# pump_control.net
KiCad netlist of a schematic drawn in EAGLE
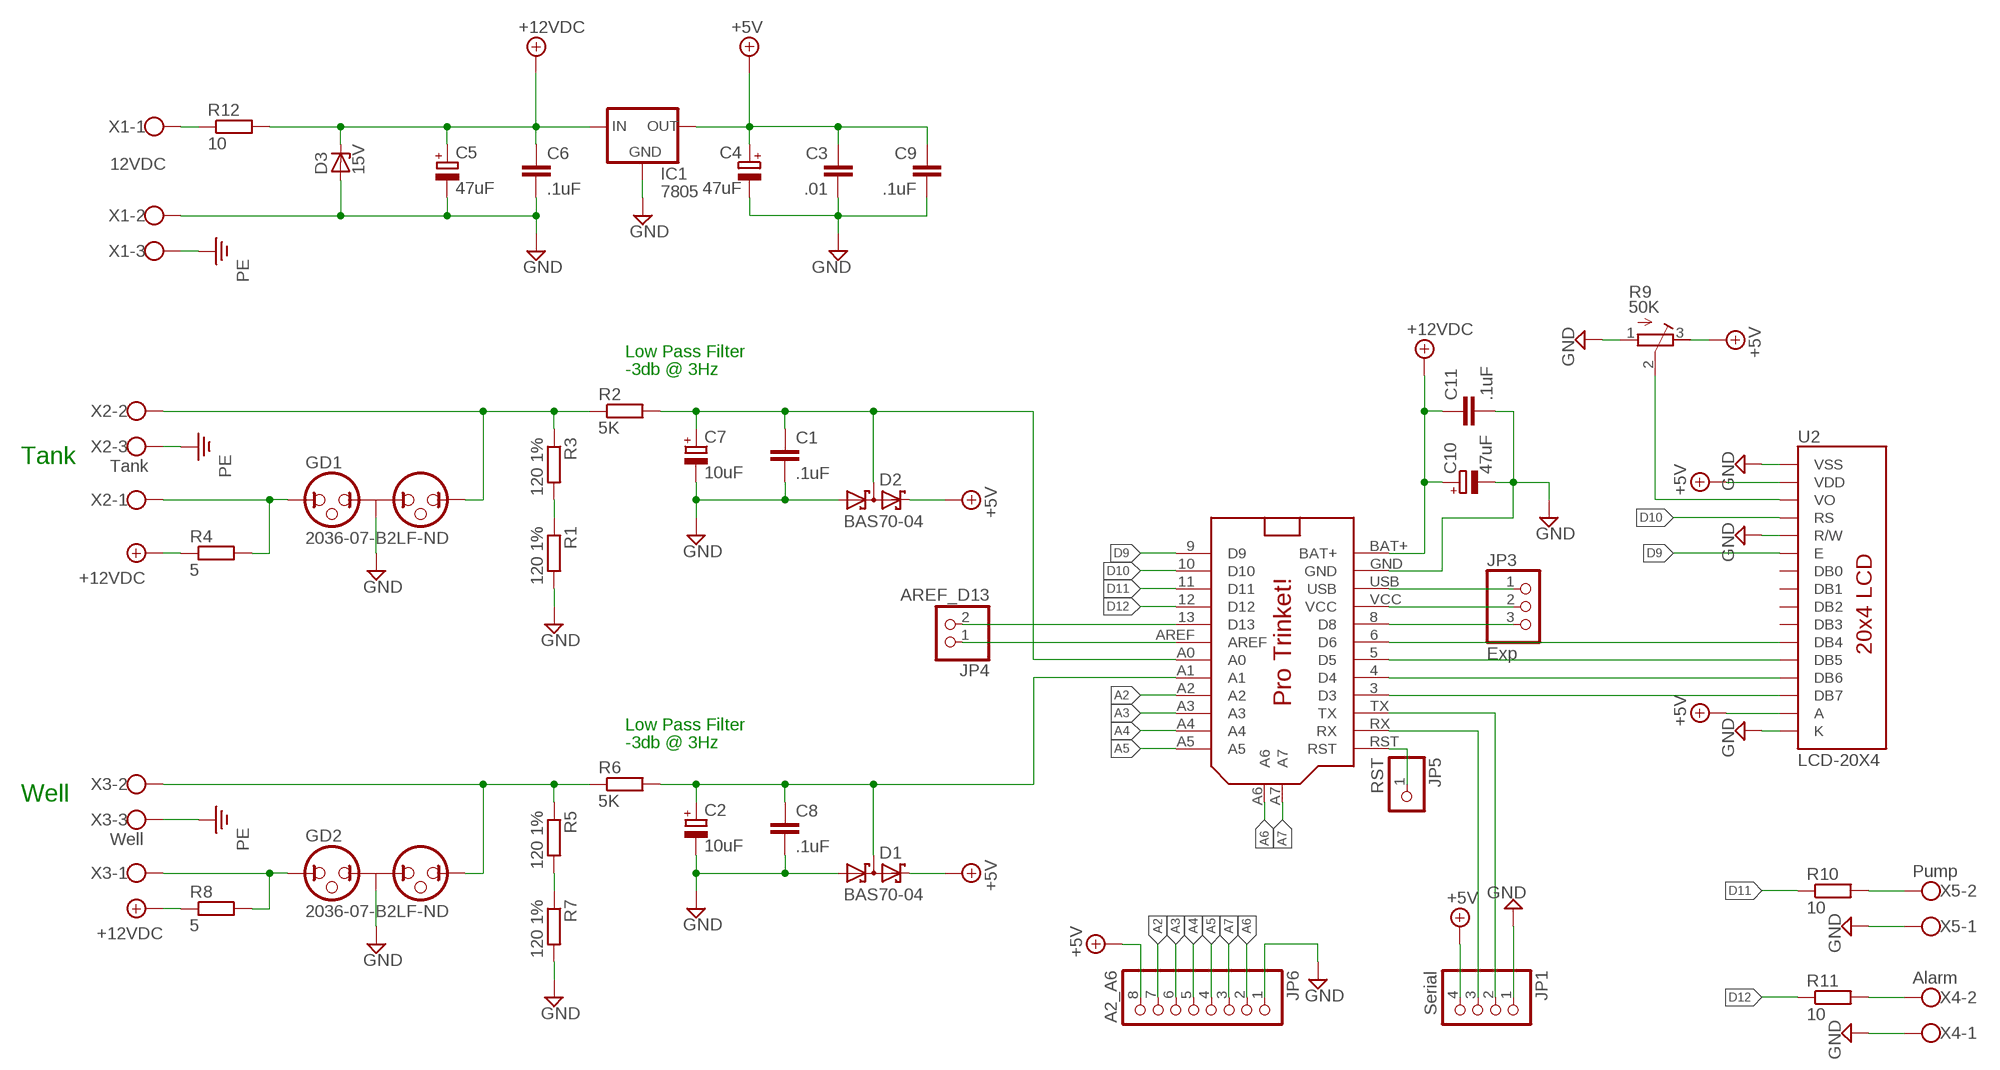
[diagram p0: schematic, sheet 1]

(export (version "E")
  (design (tool "Eeschema 10.0.6"))
  (components
    (comp (ref "C1")
      (value ".1uF")
      (footprint "eagle-import:C050-025X075")
      (libsource (lib "eagle-import") (part "C-EU050-025X075"))
    )
    (comp (ref "C2")
      (value "10uF")
      (footprint "eagle-import:E3,5-8")
      (libsource (lib "eagle-import") (part "CPOL-EUE3.5-8"))
    )
    (comp (ref "C3")
      (value ".01")
      (footprint "eagle-import:C050-025X075")
      (libsource (lib "eagle-import") (part "C-EU050-025X075"))
    )
    (comp (ref "C4")
      (value "47uF")
      (footprint "eagle-import:E3,5-8")
      (libsource (lib "eagle-import") (part "CPOL-EUE3.5-8"))
    )
    (comp (ref "C5")
      (value "47uF")
      (footprint "eagle-import:E3,5-8")
      (libsource (lib "eagle-import") (part "CPOL-EUE3.5-8"))
    )
    (comp (ref "C6")
      (value ".1uF")
      (footprint "eagle-import:C050-025X075")
      (libsource (lib "eagle-import") (part "C-EU050-025X075"))
    )
    (comp (ref "C7")
      (value "10uF")
      (footprint "eagle-import:E3,5-8")
      (libsource (lib "eagle-import") (part "CPOL-EUE3.5-8"))
    )
    (comp (ref "C8")
      (value ".1uF")
      (footprint "eagle-import:C050-025X075")
      (libsource (lib "eagle-import") (part "C-EU050-025X075"))
    )
    (comp (ref "C9")
      (value ".1uF")
      (footprint "eagle-import:C050-025X075")
      (libsource (lib "eagle-import") (part "C-EU050-025X075"))
    )
    (comp (ref "C10")
      (value "47uF")
      (footprint "eagle-import:E3,5-8")
      (libsource (lib "eagle-import") (part "CPOL-EUE3.5-8"))
    )
    (comp (ref "C11")
      (value ".1uF")
      (footprint "eagle-import:C050-025X075")
      (libsource (lib "eagle-import") (part "C-EU050-025X075"))
    )
    (comp (ref "D1")
      (value "BAS70-04")
      (footprint "eagle-import:SOT23")
      (libsource (lib "eagle-import") (part "BAS70-04"))
    )
    (comp (ref "D2")
      (value "BAS70-04")
      (footprint "eagle-import:SOT23")
      (libsource (lib "eagle-import") (part "BAS70-04"))
    )
    (comp (ref "D3")
      (value "15V")
      (footprint "eagle-import:DO35Z10")
      (libsource (lib "eagle-import") (part "ZENER-DIODEDO35Z10"))
    )
    (comp (ref "GD1")
      (value "2036-07-B2LF-ND")
      (footprint "eagle-import:2036")
      (libsource (lib "eagle-import") (part "2036_BOURNS"))
    )
    (comp (ref "GD2")
      (value "2036-07-B2LF-ND")
      (footprint "eagle-import:2036")
      (libsource (lib "eagle-import") (part "2036_BOURNS"))
    )
    (comp (ref "IC1")
      (value "7805")
      (footprint "eagle-import:78XXS")
      (libsource (lib "eagle-import") (part "78XXS"))
    )
    (comp (ref "JP1")
      (value "Serial")
      (footprint "eagle-import:1X04")
      (libsource (lib "eagle-import") (part "PINHD-1X4"))
    )
    (comp (ref "JP3")
      (value "Exp")
      (footprint "eagle-import:1X03")
      (libsource (lib "eagle-import") (part "PINHD-1X3"))
    )
    (comp (ref "JP4")
      (value "AREF_D13")
      (footprint "eagle-import:1X02")
      (libsource (lib "eagle-import") (part "PINHD-1X2"))
    )
    (comp (ref "JP5")
      (value "RST")
      (footprint "eagle-import:1X01")
      (libsource (lib "eagle-import") (part "PINHD-1X1"))
    )
    (comp (ref "JP6")
      (value "A2_A6")
      (footprint "eagle-import:1X08")
      (libsource (lib "eagle-import") (part "PINHD-1X8"))
    )
    (comp (ref "R1")
      (value "120 1%")
      (footprint "eagle-import:0207_10")
      (libsource (lib "eagle-import") (part "R-EU_0207/10"))
    )
    (comp (ref "R2")
      (value "5K")
      (footprint "eagle-import:0207_10")
      (libsource (lib "eagle-import") (part "R-EU_0207/10"))
    )
    (comp (ref "R3")
      (value "120 1%")
      (footprint "eagle-import:0207_10")
      (libsource (lib "eagle-import") (part "R-EU_0207/10"))
    )
    (comp (ref "R4")
      (value "5")
      (footprint "eagle-import:0207_10")
      (libsource (lib "eagle-import") (part "R-EU_0207/10"))
    )
    (comp (ref "R5")
      (value "120 1%")
      (footprint "eagle-import:0207_10")
      (libsource (lib "eagle-import") (part "R-EU_0207/10"))
    )
    (comp (ref "R6")
      (value "5K")
      (footprint "eagle-import:0207_10")
      (libsource (lib "eagle-import") (part "R-EU_0207/10"))
    )
    (comp (ref "R7")
      (value "120 1%")
      (footprint "eagle-import:0207_10")
      (libsource (lib "eagle-import") (part "R-EU_0207/10"))
    )
    (comp (ref "R8")
      (value "5")
      (footprint "eagle-import:0207_10")
      (libsource (lib "eagle-import") (part "R-EU_0207/10"))
    )
    (comp (ref "R9")
      (value "50K")
      (footprint "eagle-import:RTRIM64P")
      (libsource (lib "eagle-import") (part "R-TRIMM64P"))
    )
    (comp (ref "R10")
      (value "10")
      (footprint "eagle-import:0207_10")
      (libsource (lib "eagle-import") (part "R-EU_0207/10"))
    )
    (comp (ref "R11")
      (value "10")
      (footprint "eagle-import:0207_10")
      (libsource (lib "eagle-import") (part "R-EU_0207/10"))
    )
    (comp (ref "R12")
      (value "10")
      (footprint "eagle-import:0207_10")
      (libsource (lib "eagle-import") (part "R-EU_0207/10"))
    )
    (comp (ref "U1")
      (value "PRO_TRINKET")
      (footprint "eagle-import:PROTRINKET")
      (libsource (lib "eagle-import") (part "PRO_TRINKET"))
    )
    (comp (ref "U2")
      (value "LCD-20X4")
      (footprint "eagle-import:LCD-20X4-TINSHARP")
      (libsource (lib "eagle-import") (part "LCD-20X4"))
    )
    (comp (ref "X1")
      (value "12VDC")
      (footprint "eagle-import:W237-103")
      (fields (field (name "MPN") "237-103"))
      (libsource (lib "eagle-import") (part "W237-103"))
    )
    (comp (ref "X2")
      (value "Tank")
      (footprint "eagle-import:W237-103")
      (fields (field (name "MPN") "237-103"))
      (libsource (lib "eagle-import") (part "W237-103"))
    )
    (comp (ref "X3")
      (value "Well")
      (footprint "eagle-import:W237-103")
      (fields (field (name "MPN") "237-103"))
      (libsource (lib "eagle-import") (part "W237-103"))
    )
    (comp (ref "X4")
      (value "Alarm")
      (footprint "eagle-import:W237-102")
      (fields (field (name "MPN") "237-102"))
      (libsource (lib "eagle-import") (part "W237-102"))
    )
    (comp (ref "X5")
      (value "Pump")
      (footprint "eagle-import:W237-102")
      (fields (field (name "MPN") "237-102"))
      (libsource (lib "eagle-import") (part "W237-102"))
    )
  )
  (nets
    (net (code "1") (name "+5V") (class "Default")
      (node (ref "C3") (pin "1") (pinfunction "1_1") (pintype "passive"))
      (node (ref "C4") (pin "+") (pinfunction "+_+") (pintype "passive"))
      (node (ref "C9") (pin "1") (pinfunction "1_1") (pintype "passive"))
      (node (ref "D1") (pin "2") (pinfunction "C2_2") (pintype "passive"))
      (node (ref "D2") (pin "2") (pinfunction "C2_2") (pintype "passive"))
      (node (ref "IC1") (pin "OUT") (pinfunction "OUT_OUT") (pintype "passive"))
      (node (ref "JP1") (pin "4") (pinfunction "4_4") (pintype "passive"))
      (node (ref "JP6") (pin "8") (pinfunction "8_8") (pintype "passive"))
      (node (ref "R9") (pin "3") (pinfunction "E_3") (pintype "passive"))
      (node (ref "U2") (pin "15") (pinfunction "A_15") (pintype "power_in"))
      (node (ref "U2") (pin "2") (pinfunction "VDD_2") (pintype "power_in"))
    )
    (net (code "2") (name "+12VDC") (class "Default")
      (node (ref "C10") (pin "+") (pinfunction "+_+") (pintype "passive"))
      (node (ref "C11") (pin "1") (pinfunction "1_1") (pintype "passive"))
      (node (ref "C5") (pin "+") (pinfunction "+_+") (pintype "passive"))
      (node (ref "C6") (pin "1") (pinfunction "1_1") (pintype "passive"))
      (node (ref "D3") (pin "C") (pinfunction "C_C") (pintype "passive"))
      (node (ref "IC1") (pin "IN") (pinfunction "IN_IN") (pintype "input"))
      (node (ref "R12") (pin "2") (pinfunction "2_2") (pintype "passive"))
      (node (ref "R4") (pin "1") (pinfunction "1_1") (pintype "passive"))
      (node (ref "R8") (pin "1") (pinfunction "1_1") (pintype "passive"))
      (node (ref "U1") (pin "BAT+") (pinfunction "BAT+_BAT+") (pintype "power_in"))
    )
    (net (code "3") (name "A2") (class "Default")
      (node (ref "JP6") (pin "7") (pinfunction "7_7") (pintype "passive"))
      (node (ref "U1") (pin "A2") (pinfunction "A2_A2") (pintype "bidirectional"))
    )
    (net (code "4") (name "A3") (class "Default")
      (node (ref "JP6") (pin "6") (pinfunction "6_6") (pintype "passive"))
      (node (ref "U1") (pin "A3") (pinfunction "A3_A3") (pintype "bidirectional"))
    )
    (net (code "5") (name "A4") (class "Default")
      (node (ref "JP6") (pin "5") (pinfunction "5_5") (pintype "passive"))
      (node (ref "U1") (pin "A4") (pinfunction "A4_A4") (pintype "bidirectional"))
    )
    (net (code "6") (name "A5") (class "Default")
      (node (ref "JP6") (pin "4") (pinfunction "4_4") (pintype "passive"))
      (node (ref "U1") (pin "A5") (pinfunction "A5_A5") (pintype "bidirectional"))
    )
    (net (code "7") (name "A6") (class "Default")
      (node (ref "JP6") (pin "2") (pinfunction "2_2") (pintype "passive"))
      (node (ref "U1") (pin "A6") (pinfunction "A6_A6") (pintype "passive"))
    )
    (net (code "8") (name "A7") (class "Default")
      (node (ref "JP6") (pin "3") (pinfunction "3_3") (pintype "passive"))
      (node (ref "U1") (pin "A7") (pinfunction "A7_A7") (pintype "passive"))
    )
    (net (code "9") (name "D9") (class "Default")
      (node (ref "U1") (pin "9") (pinfunction "D9_9") (pintype "bidirectional"))
      (node (ref "U2") (pin "6") (pinfunction "E_6") (pintype "input"))
    )
    (net (code "10") (name "D10") (class "Default")
      (node (ref "U1") (pin "10") (pinfunction "D10_10") (pintype "bidirectional"))
      (node (ref "U2") (pin "4") (pinfunction "RS_4") (pintype "input"))
    )
    (net (code "11") (name "D11") (class "Default")
      (node (ref "R10") (pin "1") (pinfunction "1_1") (pintype "passive"))
      (node (ref "U1") (pin "11") (pinfunction "D11_11") (pintype "bidirectional"))
    )
    (net (code "12") (name "D12") (class "Default")
      (node (ref "R11") (pin "1") (pinfunction "1_1") (pintype "passive"))
      (node (ref "U1") (pin "12") (pinfunction "D12_12") (pintype "bidirectional"))
    )
    (net (code "13") (name "GND") (class "Default")
      (node (ref "C1") (pin "2") (pinfunction "2_2") (pintype "passive"))
      (node (ref "C10") (pin "-") (pinfunction "-_-") (pintype "passive"))
      (node (ref "C11") (pin "2") (pinfunction "2_2") (pintype "passive"))
      (node (ref "C2") (pin "-") (pinfunction "-_-") (pintype "passive"))
      (node (ref "C3") (pin "2") (pinfunction "2_2") (pintype "passive"))
      (node (ref "C4") (pin "-") (pinfunction "-_-") (pintype "passive"))
      (node (ref "C5") (pin "-") (pinfunction "-_-") (pintype "passive"))
      (node (ref "C6") (pin "2") (pinfunction "2_2") (pintype "passive"))
      (node (ref "C7") (pin "-") (pinfunction "-_-") (pintype "passive"))
      (node (ref "C8") (pin "2") (pinfunction "2_2") (pintype "passive"))
      (node (ref "C9") (pin "2") (pinfunction "2_2") (pintype "passive"))
      (node (ref "D1") (pin "1") (pinfunction "A1_1") (pintype "passive"))
      (node (ref "D2") (pin "1") (pinfunction "A1_1") (pintype "passive"))
      (node (ref "D3") (pin "A") (pinfunction "A_A") (pintype "passive"))
      (node (ref "GD1") (pin "P$2") (pinfunction "2_P$2") (pintype "passive"))
      (node (ref "GD2") (pin "P$2") (pinfunction "2_P$2") (pintype "passive"))
      (node (ref "IC1") (pin "GND") (pinfunction "GND_GND") (pintype "input"))
      (node (ref "JP1") (pin "1") (pinfunction "1_1") (pintype "passive"))
      (node (ref "JP6") (pin "1") (pinfunction "1_1") (pintype "passive"))
      (node (ref "R1") (pin "2") (pinfunction "2_2") (pintype "passive"))
      (node (ref "R7") (pin "2") (pinfunction "2_2") (pintype "passive"))
      (node (ref "R9") (pin "1") (pinfunction "A_1") (pintype "passive"))
      (node (ref "U1") (pin "GND") (pinfunction "GND_GND") (pintype "power_in"))
      (node (ref "U2") (pin "1") (pinfunction "VSS_1") (pintype "power_in"))
      (node (ref "U2") (pin "16") (pinfunction "K_16") (pintype "power_in"))
      (node (ref "U2") (pin "5") (pinfunction "R/W_5") (pintype "input"))
      (node (ref "X1") (pin "2") (pinfunction "KL_2") (pintype "passive"))
      (node (ref "X4") (pin "1") (pinfunction "KL_1") (pintype "passive"))
      (node (ref "X5") (pin "1") (pinfunction "KL_1") (pintype "passive"))
    )
    (net (code "14") (name "Net-(D1-C1A2)") (class "Default")
      (node (ref "C2") (pin "+") (pinfunction "+_+") (pintype "passive"))
      (node (ref "C8") (pin "1") (pinfunction "1_1") (pintype "passive"))
      (node (ref "D1") (pin "3") (pinfunction "C1A2_3") (pintype "passive"))
      (node (ref "R6") (pin "2") (pinfunction "2_2") (pintype "passive"))
      (node (ref "U1") (pin "A1") (pinfunction "A1_A1") (pintype "bidirectional"))
    )
    (net (code "15") (name "Net-(D2-C1A2)") (class "Default")
      (node (ref "C1") (pin "1") (pinfunction "1_1") (pintype "passive"))
      (node (ref "C7") (pin "+") (pinfunction "+_+") (pintype "passive"))
      (node (ref "D2") (pin "3") (pinfunction "C1A2_3") (pintype "passive"))
      (node (ref "R2") (pin "2") (pinfunction "2_2") (pintype "passive"))
      (node (ref "U1") (pin "A0") (pinfunction "A0_A0") (pintype "bidirectional"))
    )
    (net (code "16") (name "Net-(GD1-1)") (class "Default")
      (node (ref "GD1") (pin "P$1") (pinfunction "1_P$1") (pintype "passive"))
      (node (ref "R4") (pin "2") (pinfunction "2_2") (pintype "passive"))
      (node (ref "X2") (pin "1") (pinfunction "KL_1") (pintype "passive"))
    )
    (net (code "17") (name "Net-(GD1-3)") (class "Default")
      (node (ref "GD1") (pin "P$3") (pinfunction "3_P$3") (pintype "passive"))
      (node (ref "R2") (pin "1") (pinfunction "1_1") (pintype "passive"))
      (node (ref "R3") (pin "1") (pinfunction "1_1") (pintype "passive"))
      (node (ref "X2") (pin "2") (pinfunction "KL_2") (pintype "passive"))
    )
    (net (code "18") (name "Net-(GD2-1)") (class "Default")
      (node (ref "GD2") (pin "P$1") (pinfunction "1_P$1") (pintype "passive"))
      (node (ref "R8") (pin "2") (pinfunction "2_2") (pintype "passive"))
      (node (ref "X3") (pin "1") (pinfunction "KL_1") (pintype "passive"))
    )
    (net (code "19") (name "Net-(GD2-3)") (class "Default")
      (node (ref "GD2") (pin "P$3") (pinfunction "3_P$3") (pintype "passive"))
      (node (ref "R5") (pin "1") (pinfunction "1_1") (pintype "passive"))
      (node (ref "R6") (pin "1") (pinfunction "1_1") (pintype "passive"))
      (node (ref "X3") (pin "2") (pinfunction "KL_2") (pintype "passive"))
    )
    (net (code "20") (name "Net-(JP1-Pad2)") (class "Default")
      (node (ref "JP1") (pin "2") (pinfunction "2_2") (pintype "passive"))
      (node (ref "U1") (pin "TX") (pinfunction "TX_TX") (pintype "bidirectional"))
    )
    (net (code "21") (name "Net-(JP1-Pad3)") (class "Default")
      (node (ref "JP1") (pin "3") (pinfunction "3_3") (pintype "passive"))
      (node (ref "U1") (pin "RX") (pinfunction "RX_RX") (pintype "bidirectional"))
    )
    (net (code "22") (name "Net-(JP3-Pad1)") (class "Default")
      (node (ref "JP3") (pin "1") (pinfunction "1_1") (pintype "passive"))
      (node (ref "U1") (pin "USB") (pinfunction "USB_USB") (pintype "power_in"))
    )
    (net (code "23") (name "Net-(JP3-Pad2)") (class "Default")
      (node (ref "JP3") (pin "2") (pinfunction "2_2") (pintype "passive"))
      (node (ref "U1") (pin "VCC") (pinfunction "VCC_VCC") (pintype "power_in"))
    )
    (net (code "24") (name "Net-(JP4-Pad1)") (class "Default")
      (node (ref "JP4") (pin "1") (pinfunction "1_1") (pintype "passive"))
      (node (ref "U1") (pin "AREF") (pinfunction "AREF_AREF") (pintype "passive"))
    )
    (net (code "25") (name "Net-(JP5-Pad1)") (class "Default")
      (node (ref "JP5") (pin "1") (pinfunction "1_1") (pintype "passive"))
      (node (ref "U1") (pin "RST") (pinfunction "RST_RST") (pintype "passive"))
    )
    (net (code "26") (name "Net-(R1-Pad1)") (class "Default")
      (node (ref "R1") (pin "1") (pinfunction "1_1") (pintype "passive"))
      (node (ref "R3") (pin "2") (pinfunction "2_2") (pintype "passive"))
    )
    (net (code "27") (name "Net-(R5-Pad2)") (class "Default")
      (node (ref "R5") (pin "2") (pinfunction "2_2") (pintype "passive"))
      (node (ref "R7") (pin "1") (pinfunction "1_1") (pintype "passive"))
    )
    (net (code "28") (name "Net-(R9-S)") (class "Default")
      (node (ref "R9") (pin "2") (pinfunction "S_2") (pintype "passive"))
      (node (ref "U2") (pin "3") (pinfunction "VO_3") (pintype "bidirectional"))
    )
    (net (code "29") (name "Net-(U1-D3)") (class "Default")
      (node (ref "U1") (pin "3") (pinfunction "D3_3") (pintype "bidirectional"))
      (node (ref "U2") (pin "14") (pinfunction "DB7_14") (pintype "bidirectional"))
    )
    (net (code "30") (name "Net-(U1-D4)") (class "Default")
      (node (ref "U1") (pin "4") (pinfunction "D4_4") (pintype "bidirectional"))
      (node (ref "U2") (pin "13") (pinfunction "DB6_13") (pintype "bidirectional"))
    )
    (net (code "31") (name "Net-(U1-D5)") (class "Default")
      (node (ref "U1") (pin "5") (pinfunction "D5_5") (pintype "bidirectional"))
      (node (ref "U2") (pin "12") (pinfunction "DB5_12") (pintype "bidirectional"))
    )
    (net (code "32") (name "Net-(U1-D6)") (class "Default")
      (node (ref "U1") (pin "6") (pinfunction "D6_6") (pintype "bidirectional"))
      (node (ref "U2") (pin "11") (pinfunction "DB4_11") (pintype "bidirectional"))
    )
    (net (code "33") (name "Net-(U1-D8)") (class "Default")
      (node (ref "JP3") (pin "3") (pinfunction "3_3") (pintype "passive"))
      (node (ref "U1") (pin "8") (pinfunction "D8_8") (pintype "bidirectional"))
    )
    (net (code "34") (name "Net-(U1-D13)") (class "Default")
      (node (ref "JP4") (pin "2") (pinfunction "2_2") (pintype "passive"))
      (node (ref "U1") (pin "13") (pinfunction "D13_13") (pintype "bidirectional"))
    )
    (net (code "35") (name "Net-(X1A-KL)") (class "Default")
      (node (ref "R12") (pin "1") (pinfunction "1_1") (pintype "passive"))
      (node (ref "X1") (pin "1") (pinfunction "KL_1") (pintype "passive"))
    )
    (net (code "36") (name "Net-(X4B-KL)") (class "Default")
      (node (ref "R11") (pin "2") (pinfunction "2_2") (pintype "passive"))
      (node (ref "X4") (pin "2") (pinfunction "KL_2") (pintype "passive"))
    )
    (net (code "37") (name "Net-(X5B-KL)") (class "Default")
      (node (ref "R10") (pin "2") (pinfunction "2_2") (pintype "passive"))
      (node (ref "X5") (pin "2") (pinfunction "KL_2") (pintype "passive"))
    )
    (net (code "38") (name "PE") (class "Default")
      (node (ref "X1") (pin "3") (pinfunction "KL_3") (pintype "passive"))
      (node (ref "X2") (pin "3") (pinfunction "KL_3") (pintype "passive"))
      (node (ref "X3") (pin "3") (pinfunction "KL_3") (pintype "passive"))
    )
    (net (code "39") (name "unconnected-(U2-DB0-Pad7)") (class "Default")
      (node (ref "U2") (pin "7") (pinfunction "DB0_7") (pintype "bidirectional"))
    )
    (net (code "40") (name "unconnected-(U2-DB1-Pad8)") (class "Default")
      (node (ref "U2") (pin "8") (pinfunction "DB1_8") (pintype "bidirectional"))
    )
    (net (code "41") (name "unconnected-(U2-DB2-Pad9)") (class "Default")
      (node (ref "U2") (pin "9") (pinfunction "DB2_9") (pintype "bidirectional"))
    )
    (net (code "42") (name "unconnected-(U2-DB3-Pad10)") (class "Default")
      (node (ref "U2") (pin "10") (pinfunction "DB3_10") (pintype "bidirectional"))
    )
  )
)
